# airball_sensor_board_v8_main.net
KiCad netlist of a schematic drawn in EAGLE
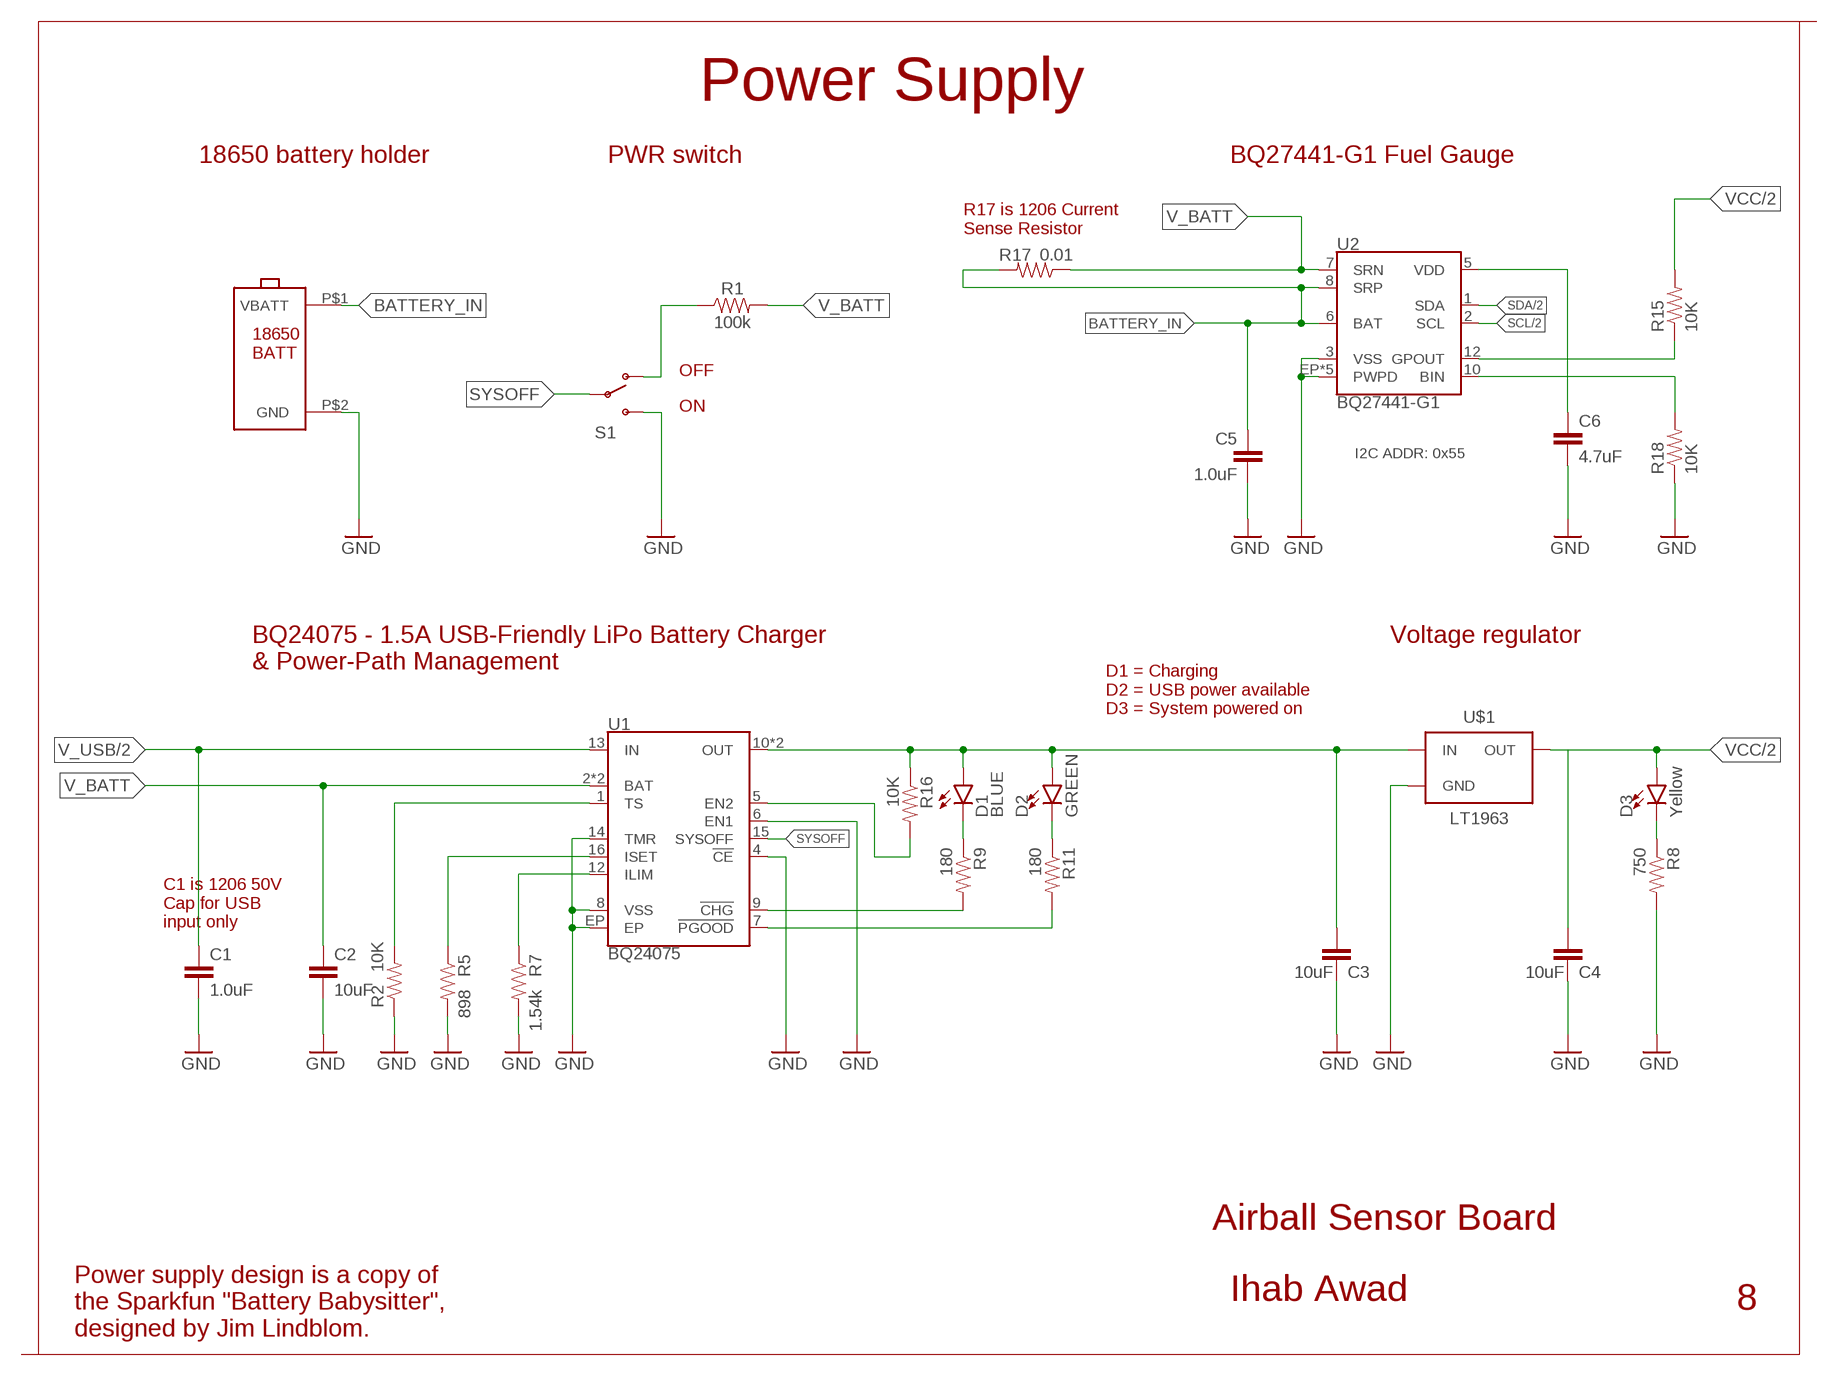
[diagram p0: schematic, sheet 1]
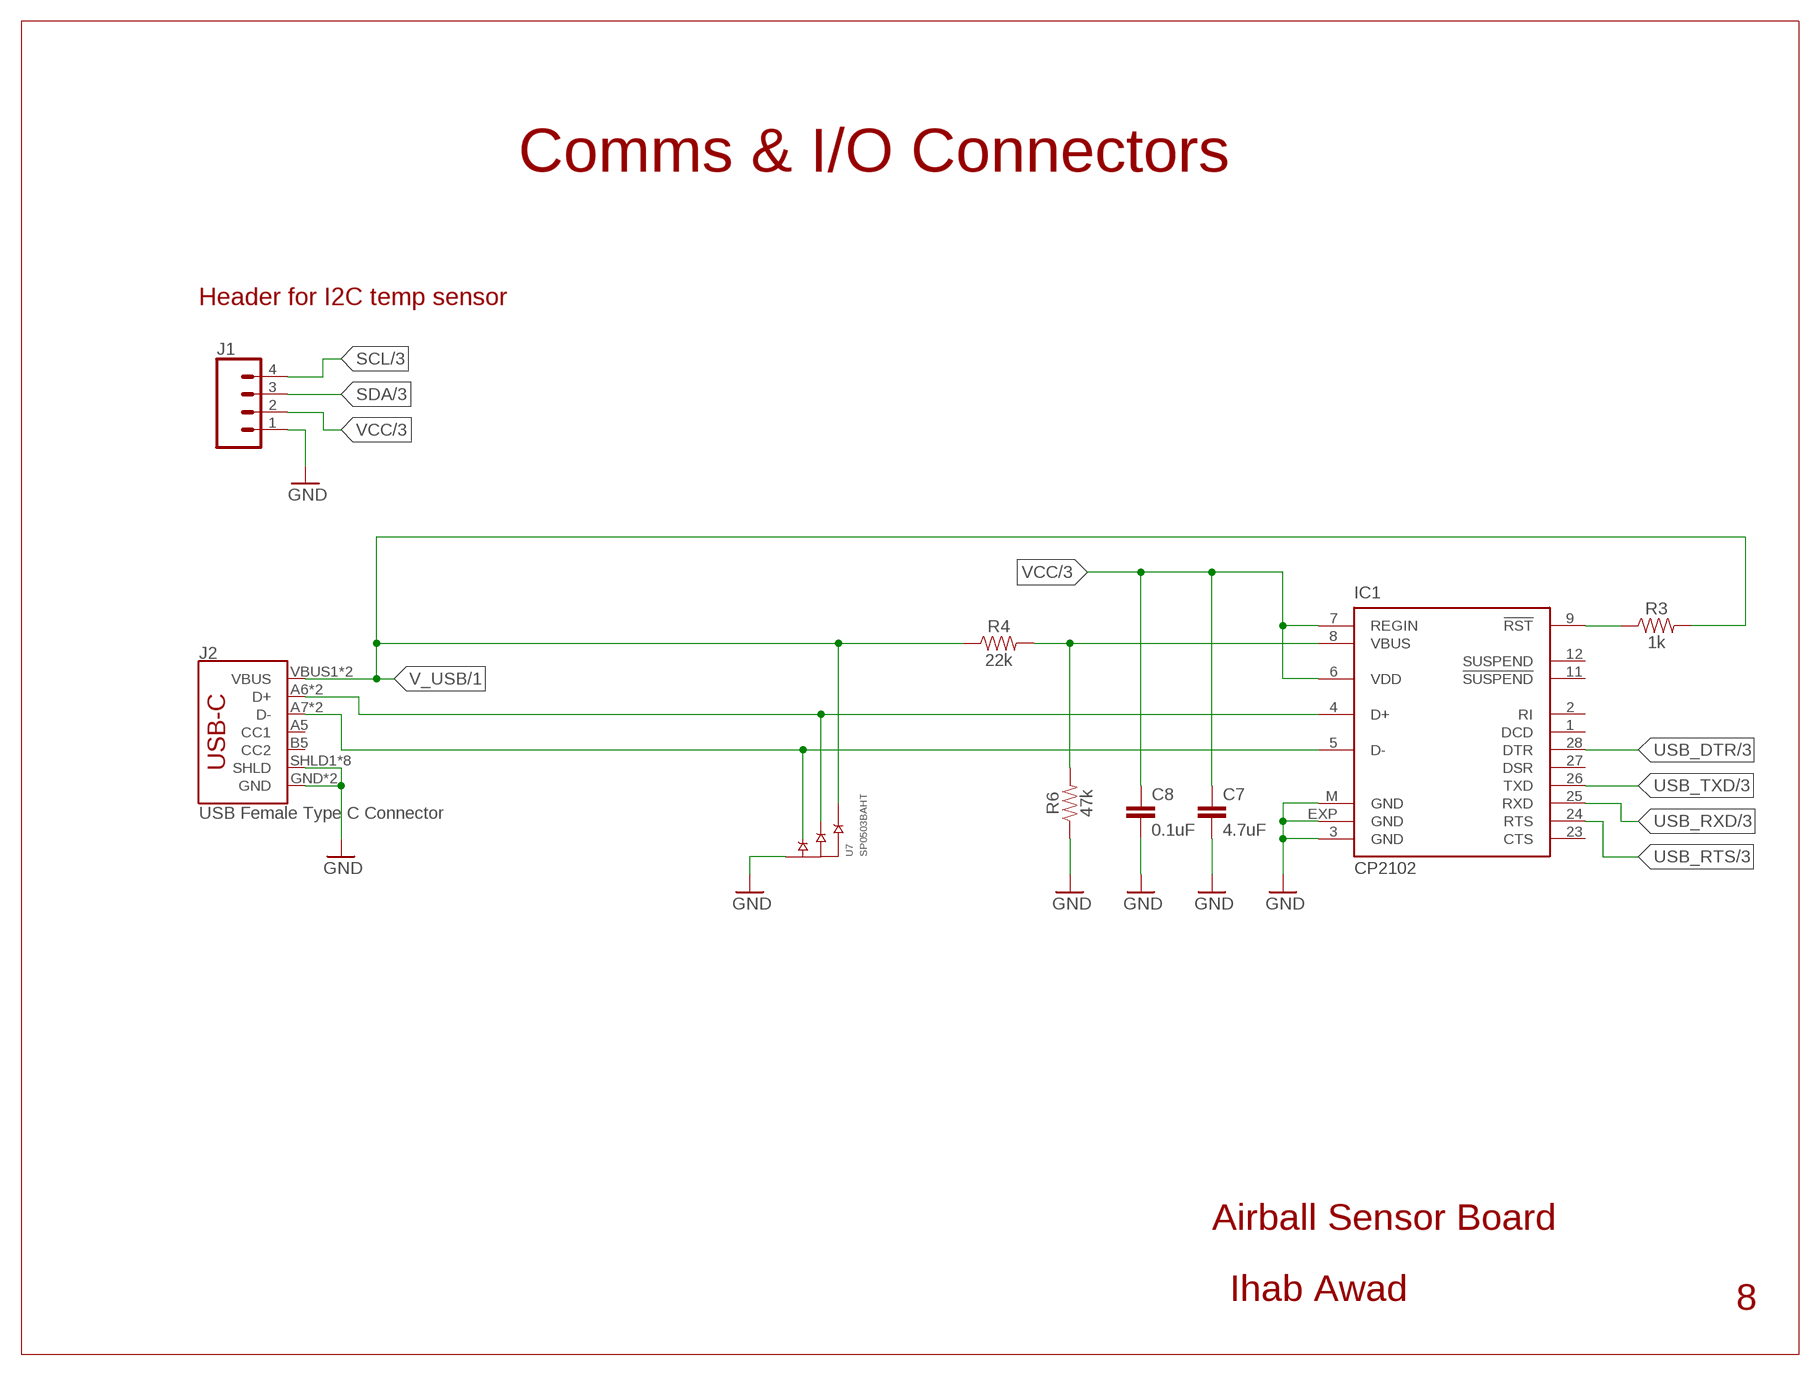
[diagram p1: schematic, sheet 2]
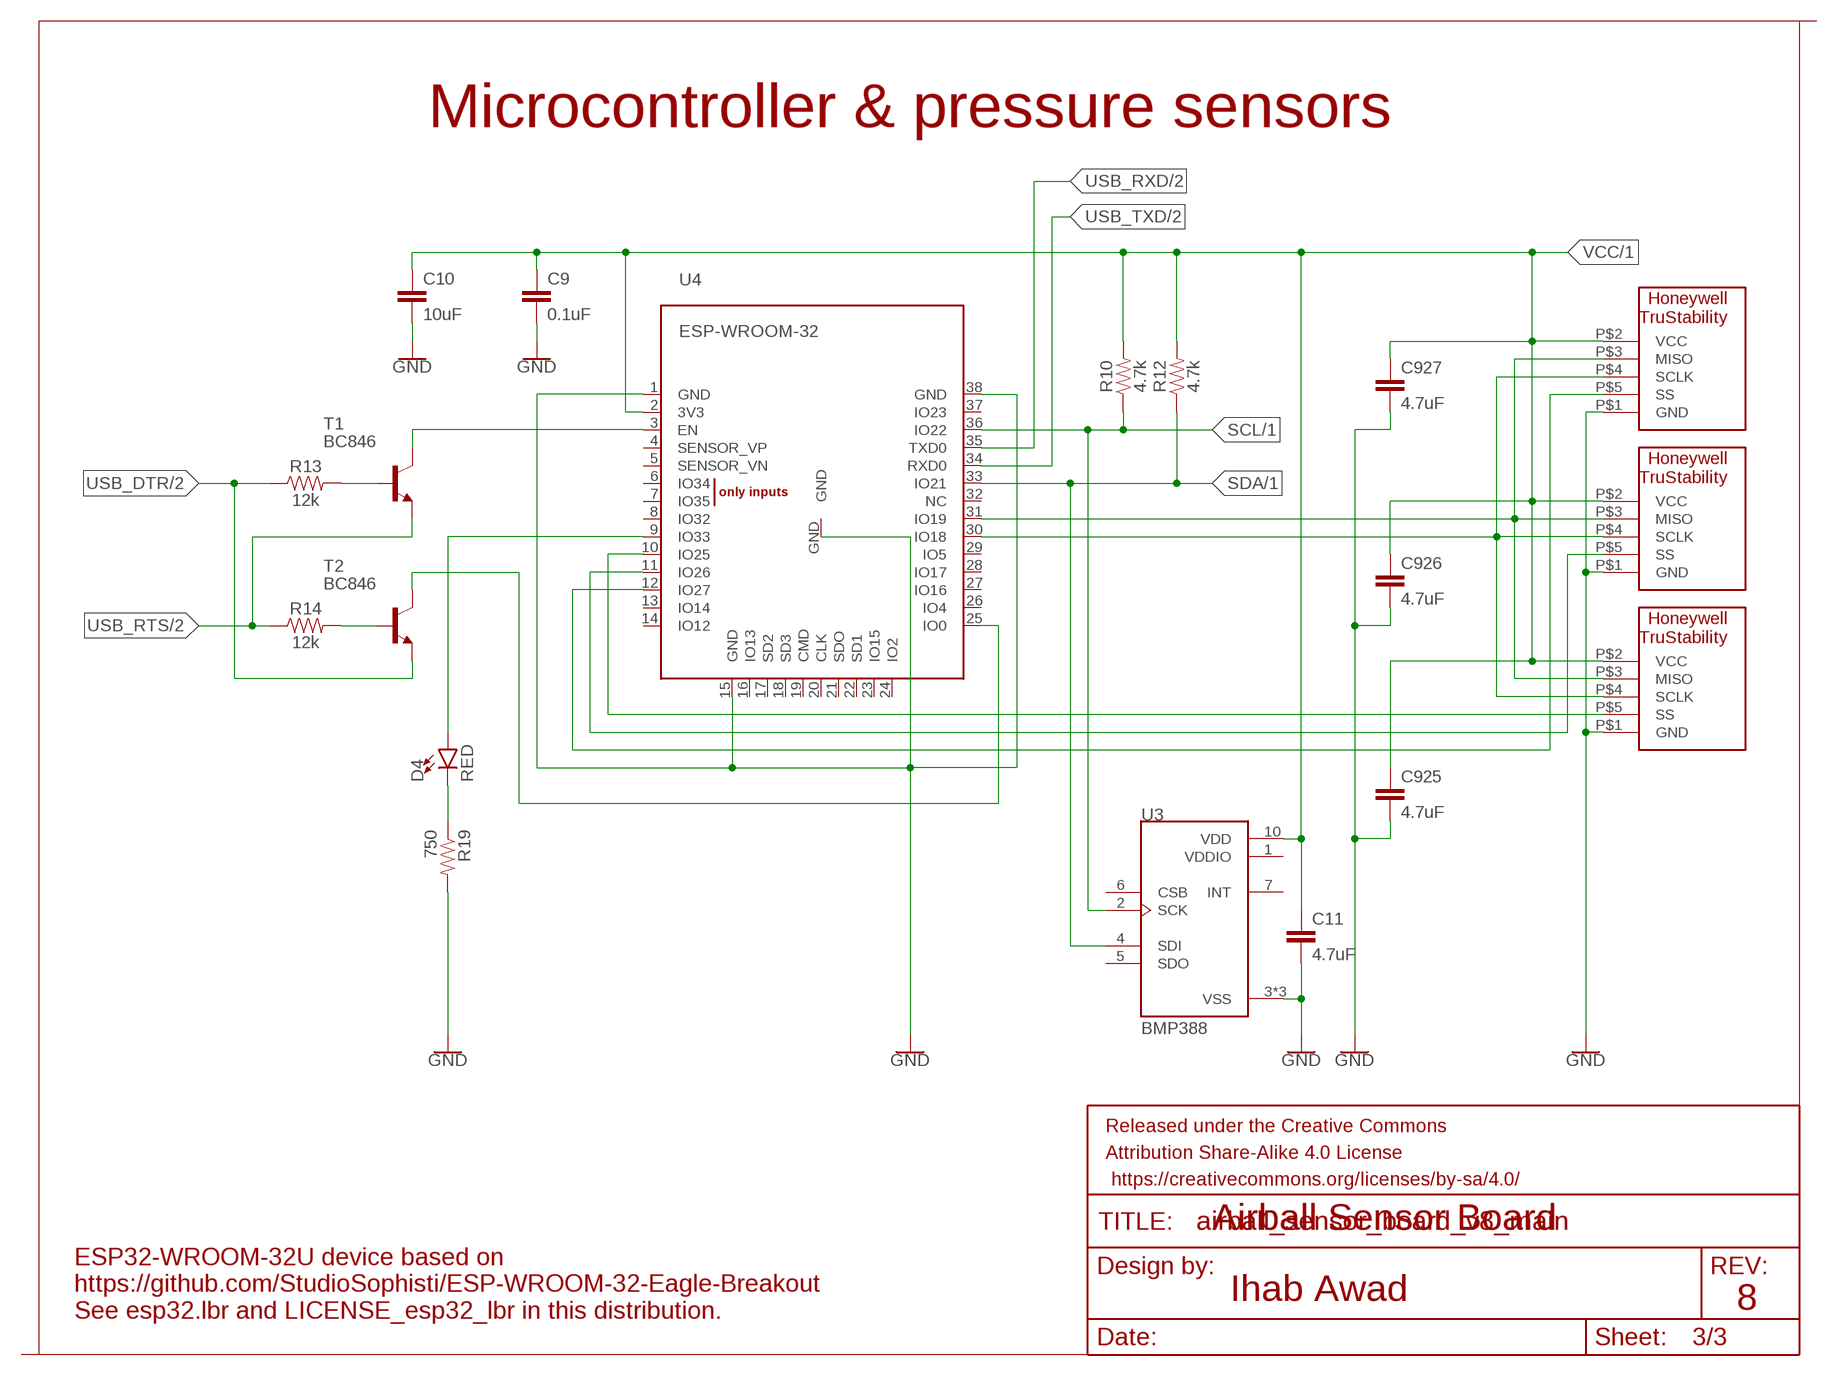
[diagram p2: schematic, sheet 3]

(export (version "E")
  (design (tool "Eeschema 10.0.6"))
  (components
    (comp (ref "C7")
      (value "4.7uF")
      (footprint "eagle-import:0603")
      (libsource (lib "eagle-import") (part "4.7UF-0603-35V-(20%)"))
    )
    (comp (ref "C8")
      (value "0.1uF")
      (footprint "eagle-import:0603")
      (libsource (lib "eagle-import") (part "0.1UF-0603-25V-(+80/-20%)"))
    )
    (comp (ref "IC1")
      (value "CP2102")
      (footprint "eagle-import:MLP28")
      (fields (field (name "MF") "FARNELL") (field (name "MPN") "CP2102-GM"))
      (libsource (lib "eagle-import") (part "CP2102"))
    )
    (comp (ref "J1")
      (value "CONN_04JST-PTH")
      (footprint "eagle-import:JST-4-PTH")
      (libsource (lib "eagle-import") (part "CONN_04JST-PTH"))
    )
    (comp (ref "J2")
      (value "USB Female Type C Connector")
      (footprint "eagle-import:USB-C-16P")
      (libsource (lib "eagle-import") (part "USB_C"))
    )
    (comp (ref "R3")
      (value "1k")
      (footprint "eagle-import:0603")
      (libsource (lib "eagle-import") (part "1KOHM-0603-1/10W-1%"))
    )
    (comp (ref "R4")
      (value "22k")
      (footprint "eagle-import:0603")
      (libsource (lib "eagle-import") (part "22KOHM-0603-1/10W-1%"))
    )
    (comp (ref "R6")
      (value "47k")
      (footprint "eagle-import:0603")
      (libsource (lib "eagle-import") (part "47KOHM-0603-1/10W-1%"))
    )
    (comp (ref "U7")
      (value "SP0503BAHT")
      (footprint "eagle-import:SOT143")
      (fields (field (name "DIGI-KEY_PART_NUMBER") "F2715TR-ND") (field (name "MF") "Littelfuse Inc."))
      (libsource (lib "eagle-import") (part "SP0503BAHT"))
    )
    (comp (ref "C9")
      (value "0.1uF")
      (footprint "eagle-import:0603")
      (libsource (lib "eagle-import") (part "0.1UF-0603-25V-(+80/-20%)"))
    )
    (comp (ref "C10")
      (value "10uF")
      (footprint "eagle-import:0603")
      (libsource (lib "eagle-import") (part "10UF-0603-6.3V-20%"))
    )
    (comp (ref "C11")
      (value "4.7uF")
      (footprint "eagle-import:0603")
      (libsource (lib "eagle-import") (part "4.7UF-0603-6.3V-(10%)"))
    )
    (comp (ref "C925")
      (value "4.7uF")
      (footprint "eagle-import:0603")
      (libsource (lib "eagle-import") (part "4.7UF-0603-6.3V-(10%)"))
    )
    (comp (ref "C926")
      (value "4.7uF")
      (footprint "eagle-import:0603")
      (libsource (lib "eagle-import") (part "4.7UF-0603-6.3V-(10%)"))
    )
    (comp (ref "C927")
      (value "4.7uF")
      (footprint "eagle-import:0603")
      (libsource (lib "eagle-import") (part "4.7UF-0603-6.3V-(10%)"))
    )
    (comp (ref "D4")
      (value "RED")
      (footprint "eagle-import:LED-0603")
      (libsource (lib "eagle-import") (part "LED-RED0603"))
    )
    (comp (ref "FRAME3")
      (value "FRAME-LETTER")
      (footprint "eagle-import:CREATIVE_COMMONS")
      (libsource (lib "eagle-import") (part "FRAME-LETTER"))
    )
    (comp (ref "R10")
      (value "4.7k")
      (footprint "eagle-import:0603")
      (libsource (lib "eagle-import") (part "4.7KOHM-0603-1/10W-1%"))
    )
    (comp (ref "R12")
      (value "4.7k")
      (footprint "eagle-import:0603")
      (libsource (lib "eagle-import") (part "4.7KOHM-0603-1/10W-1%"))
    )
    (comp (ref "R13")
      (value "12k")
      (footprint "eagle-import:0603")
      (libsource (lib "eagle-import") (part "12KOHM-0603-1/10W-1%"))
    )
    (comp (ref "R14")
      (value "12k")
      (footprint "eagle-import:0603")
      (libsource (lib "eagle-import") (part "12KOHM-0603-1/10W-1%"))
    )
    (comp (ref "R19")
      (value "750")
      (footprint "eagle-import:0603-RES")
      (libsource (lib "eagle-import") (part "10KOHM-1/10W-1%(0603)0603"))
    )
    (comp (ref "T1")
      (value "BC846")
      (footprint "eagle-import:SOT23")
      (libsource (lib "eagle-import") (part "BC846"))
    )
    (comp (ref "T2")
      (value "BC846")
      (footprint "eagle-import:SOT23")
      (libsource (lib "eagle-import") (part "BC846"))
    )
    (comp (ref "U$925")
      (value "HONEYWELL_HSC_SMT")
      (footprint "eagle-import:HONEYWELL_HSC_SMT")
      (libsource (lib "eagle-import") (part "HONEYWELL_HSC_SMT"))
    )
    (comp (ref "U$926")
      (value "HONEYWELL_HSC_SMT")
      (footprint "eagle-import:HONEYWELL_HSC_SMT")
      (libsource (lib "eagle-import") (part "HONEYWELL_HSC_SMT"))
    )
    (comp (ref "U$927")
      (value "HONEYWELL_HSC_SMT")
      (footprint "eagle-import:HONEYWELL_HSC_SMT")
      (libsource (lib "eagle-import") (part "HONEYWELL_HSC_SMT"))
    )
    (comp (ref "U3")
      (value "BMP388")
      (footprint "eagle-import:PQFN50P200X200X80-10N")
      (fields (field (name "MF") "Bosch Sensortec"))
      (libsource (lib "eagle-import") (part "BMP388"))
    )
    (comp (ref "U4")
      (value "ESP-WROOM-32")
      (footprint "eagle-import:ESP-WROOM-32")
      (libsource (lib "eagle-import") (part "ESP-WROOM-32"))
    )
    (comp (ref "C1")
      (value "1.0uF")
      (footprint "eagle-import:1206-CAP")
      (libsource (lib "eagle-import") (part "1.0UF50V10%(1206)"))
    )
    (comp (ref "C2")
      (value "10uF")
      (footprint "eagle-import:0805-CAP")
      (libsource (lib "eagle-import") (part "10UF10V10%(0805)"))
    )
    (comp (ref "C3")
      (value "10uF")
      (footprint "eagle-import:0805-CAP")
      (libsource (lib "eagle-import") (part "10UF10V10%(0805)"))
    )
    (comp (ref "C4")
      (value "10uF")
      (footprint "eagle-import:0805-CAP")
      (libsource (lib "eagle-import") (part "10UF10V10%(0805)"))
    )
    (comp (ref "C5")
      (value "1.0uF")
      (footprint "eagle-import:0603-CAP")
      (libsource (lib "eagle-import") (part "1.0UF-16V-10%(0603)"))
    )
    (comp (ref "C6")
      (value "4.7uF")
      (footprint "eagle-import:0603")
      (libsource (lib "eagle-import") (part "4.7UF-0603-35V-(20%)"))
    )
    (comp (ref "D1")
      (value "BLUE")
      (footprint "eagle-import:LED-0603")
      (libsource (lib "eagle-import") (part "LED-BLUE0603"))
    )
    (comp (ref "D2")
      (value "GREEN")
      (footprint "eagle-import:LED-0603")
      (libsource (lib "eagle-import") (part "LED-GREEN0603"))
    )
    (comp (ref "D3")
      (value "Yellow")
      (footprint "eagle-import:LED-0603")
      (libsource (lib "eagle-import") (part "LED-YELLOW0603"))
    )
    (comp (ref "R1")
      (value "100k")
      (footprint "eagle-import:0603")
      (libsource (lib "eagle-import") (part "100KOHM-0603-1/10W-1%"))
    )
    (comp (ref "R2")
      (value "10K")
      (footprint "eagle-import:0603-RES")
      (libsource (lib "eagle-import") (part "10KOHM-1/10W-1%(0603)0603"))
    )
    (comp (ref "R5")
      (value "898")
      (footprint "eagle-import:0603-RES")
      (libsource (lib "eagle-import") (part "RESISTOR0603-RES"))
    )
    (comp (ref "R7")
      (value "1.54k")
      (footprint "eagle-import:0603-RES")
      (libsource (lib "eagle-import") (part "RESISTOR0603-RES"))
    )
    (comp (ref "R8")
      (value "750")
      (footprint "eagle-import:0603-RES")
      (libsource (lib "eagle-import") (part "10KOHM-1/10W-1%(0603)0603"))
    )
    (comp (ref "R9")
      (value "180")
      (footprint "eagle-import:0603-RES")
      (libsource (lib "eagle-import") (part "180OHM1/10W1%(0603)"))
    )
    (comp (ref "R11")
      (value "180")
      (footprint "eagle-import:0603-RES")
      (libsource (lib "eagle-import") (part "180OHM1/10W1%(0603)"))
    )
    (comp (ref "R15")
      (value "10K")
      (footprint "eagle-import:0603-RES")
      (libsource (lib "eagle-import") (part "10KOHM-1/10W-1%(0603)0603"))
    )
    (comp (ref "R16")
      (value "10K")
      (footprint "eagle-import:0603-RES")
      (libsource (lib "eagle-import") (part "10KOHM-1/10W-1%(0603)0603"))
    )
    (comp (ref "R17")
      (value "0.01")
      (footprint "eagle-import:1206")
      (libsource (lib "eagle-import") (part "SparkFun-Resistors_RESISTOR1206"))
    )
    (comp (ref "R18")
      (value "10K")
      (footprint "eagle-import:0603-RES")
      (libsource (lib "eagle-import") (part "10KOHM-1/10W-1%(0603)0603"))
    )
    (comp (ref "S1")
      (value "SWITCH-SPDTSMD")
      (footprint "eagle-import:SWITCH_SPDT_SMD")
      (libsource (lib "eagle-import") (part "SWITCH-SPDTSMD"))
    )
    (comp (ref "U$1")
      (value "LT1963")
      (footprint "eagle-import:SOT223-3")
      (libsource (lib "eagle-import") (part "LT1963"))
    )
    (comp (ref "U$2")
      (value "KEYSTONE_1042P_18650_BATT_HOLDER")
      (footprint "eagle-import:KEYSTONE_1042P_18650_BATT_HOLDER")
      (libsource (lib "eagle-import") (part "KEYSTONE_1042P_18650_BATT_HOLDER"))
    )
    (comp (ref "U1")
      (value "BQ24075")
      (footprint "eagle-import:PVQFN-N16")
      (libsource (lib "eagle-import") (part "BQ24075"))
    )
    (comp (ref "U2")
      (value "BQ27441-G1")
      (footprint "eagle-import:PDSO-N12")
      (libsource (lib "eagle-import") (part "BQ27441-G1"))
    )
  )
  (nets
    (net (code "1") (name "BATTERY_IN") (class "Default")
      (node (ref "C5") (pin "1") (pinfunction "1_1") (pintype "passive"))
      (node (ref "R17") (pin "2") (pinfunction "2_2") (pintype "passive"))
      (node (ref "U$2") (pin "P$1") (pinfunction "VBATT_P$1") (pintype "bidirectional"))
      (node (ref "U2") (pin "6") (pinfunction "BAT_6") (pintype "bidirectional"))
      (node (ref "U2") (pin "8") (pinfunction "SRP_8") (pintype "bidirectional"))
    )
    (net (code "2") (name "GND") (class "Default")
      (node (ref "C1") (pin "2") (pinfunction "2_2") (pintype "passive"))
      (node (ref "C10") (pin "2") (pinfunction "2_2") (pintype "passive"))
      (node (ref "C11") (pin "2") (pinfunction "2_2") (pintype "passive"))
      (node (ref "C2") (pin "2") (pinfunction "2_2") (pintype "passive"))
      (node (ref "C3") (pin "2") (pinfunction "2_2") (pintype "passive"))
      (node (ref "C4") (pin "2") (pinfunction "2_2") (pintype "passive"))
      (node (ref "C5") (pin "2") (pinfunction "2_2") (pintype "passive"))
      (node (ref "C6") (pin "2") (pinfunction "2_2") (pintype "passive"))
      (node (ref "C7") (pin "2") (pinfunction "2_2") (pintype "passive"))
      (node (ref "C8") (pin "2") (pinfunction "2_2") (pintype "passive"))
      (node (ref "C9") (pin "2") (pinfunction "2_2") (pintype "passive"))
      (node (ref "C925") (pin "2") (pinfunction "2_2") (pintype "passive"))
      (node (ref "C926") (pin "2") (pinfunction "2_2") (pintype "passive"))
      (node (ref "C927") (pin "2") (pinfunction "2_2") (pintype "passive"))
      (node (ref "IC1") (pin "3") (pinfunction "GND_3") (pintype "power_in"))
      (node (ref "IC1") (pin "EXP") (pinfunction "GND_EXP") (pintype "power_in"))
      (node (ref "IC1") (pin "M") (pinfunction "GND_M") (pintype "power_in"))
      (node (ref "J1") (pin "1") (pinfunction "1_1") (pintype "passive"))
      (node (ref "J2") (pin "GND") (pinfunction "GND_GND") (pintype "bidirectional"))
      (node (ref "J2") (pin "GND2") (pinfunction "GND_GND2") (pintype "bidirectional"))
      (node (ref "J2") (pin "SHLD1") (pinfunction "SHLD_SHLD1") (pintype "bidirectional"))
      (node (ref "J2") (pin "SHLD2") (pinfunction "SHLD_SHLD2") (pintype "bidirectional"))
      (node (ref "J2") (pin "SHLD3") (pinfunction "SHLD_SHLD3") (pintype "bidirectional"))
      (node (ref "J2") (pin "SHLD4") (pinfunction "SHLD_SHLD4") (pintype "bidirectional"))
      (node (ref "J2") (pin "SHLD5") (pinfunction "SHLD_SHLD5") (pintype "bidirectional"))
      (node (ref "J2") (pin "SHLD6") (pinfunction "SHLD_SHLD6") (pintype "bidirectional"))
      (node (ref "J2") (pin "SHLD7") (pinfunction "SHLD_SHLD7") (pintype "bidirectional"))
      (node (ref "J2") (pin "SHLD8") (pinfunction "SHLD_SHLD8") (pintype "bidirectional"))
      (node (ref "R18") (pin "1") (pinfunction "1_1") (pintype "passive"))
      (node (ref "R19") (pin "2") (pinfunction "2_2") (pintype "passive"))
      (node (ref "R2") (pin "1") (pinfunction "1_1") (pintype "passive"))
      (node (ref "R5") (pin "2") (pinfunction "2_2") (pintype "passive"))
      (node (ref "R6") (pin "1") (pinfunction "1_1") (pintype "passive"))
      (node (ref "R7") (pin "2") (pinfunction "2_2") (pintype "passive"))
      (node (ref "R8") (pin "2") (pinfunction "2_2") (pintype "passive"))
      (node (ref "S1") (pin "3") (pinfunction "S_3") (pintype "passive"))
      (node (ref "U$1") (pin "2") (pinfunction "GND_2") (pintype "power_in"))
      (node (ref "U$1") (pin "TAB") (pinfunction "GND_TAB") (pintype "power_in"))
      (node (ref "U$2") (pin "P$2") (pinfunction "GND_P$2") (pintype "bidirectional"))
      (node (ref "U$925") (pin "P$1") (pinfunction "GND_P$1") (pintype "bidirectional"))
      (node (ref "U$926") (pin "P$1") (pinfunction "GND_P$1") (pintype "bidirectional"))
      (node (ref "U$927") (pin "P$1") (pinfunction "GND_P$1") (pintype "bidirectional"))
      (node (ref "U1") (pin "14") (pinfunction "TMR_14") (pintype "bidirectional"))
      (node (ref "U1") (pin "4") (pinfunction "~{CE}_4") (pintype "bidirectional"))
      (node (ref "U1") (pin "6") (pinfunction "EN1_6") (pintype "bidirectional"))
      (node (ref "U1") (pin "8") (pinfunction "VSS_8") (pintype "bidirectional"))
      (node (ref "U1") (pin "EP") (pinfunction "EP_EP") (pintype "bidirectional"))
      (node (ref "U2") (pin "3") (pinfunction "VSS_3") (pintype "bidirectional"))
      (node (ref "U2") (pin "EP") (pinfunction "PWPD_EP") (pintype "bidirectional"))
      (node (ref "U2") (pin "EP1") (pinfunction "PWPD_EP1") (pintype "bidirectional"))
      (node (ref "U2") (pin "EP2") (pinfunction "PWPD_EP2") (pintype "bidirectional"))
      (node (ref "U2") (pin "EP3") (pinfunction "PWPD_EP3") (pintype "bidirectional"))
      (node (ref "U2") (pin "EP4") (pinfunction "PWPD_EP4") (pintype "bidirectional"))
      (node (ref "U3") (pin "3") (pinfunction "VSS_3") (pintype "power_in"))
      (node (ref "U3") (pin "8") (pinfunction "VSS_8") (pintype "power_in"))
      (node (ref "U3") (pin "9") (pinfunction "VSS_9") (pintype "power_in"))
      (node (ref "U4") (pin "1") (pinfunction "GND_1") (pintype "bidirectional"))
      (node (ref "U4") (pin "15") (pinfunction "GND_15") (pintype "bidirectional"))
      (node (ref "U4") (pin "38") (pinfunction "GND_38") (pintype "bidirectional"))
      (node (ref "U4") (pin "GND") (pinfunction "GND_GND") (pintype "bidirectional"))
      (node (ref "U7") (pin "1") (pinfunction "GND_1") (pintype "bidirectional"))
    )
    (net (code "3") (name "Net-(D1-PadC)") (class "Default")
      (node (ref "D1") (pin "C") (pinfunction "C_C") (pintype "passive"))
      (node (ref "R9") (pin "1") (pinfunction "1_1") (pintype "passive"))
    )
    (net (code "4") (name "Net-(D2-PadC)") (class "Default")
      (node (ref "D2") (pin "C") (pinfunction "C_C") (pintype "passive"))
      (node (ref "R11") (pin "1") (pinfunction "1_1") (pintype "passive"))
    )
    (net (code "5") (name "Net-(D3-PadC)") (class "Default")
      (node (ref "D3") (pin "C") (pinfunction "C_C") (pintype "passive"))
      (node (ref "R8") (pin "1") (pinfunction "1_1") (pintype "passive"))
    )
    (net (code "6") (name "Net-(D4-PadC)") (class "Default")
      (node (ref "D4") (pin "C") (pinfunction "C_C") (pintype "passive"))
      (node (ref "R19") (pin "1") (pinfunction "1_1") (pintype "passive"))
    )
    (net (code "7") (name "Net-(IC1-D+)") (class "Default")
      (node (ref "IC1") (pin "4") (pinfunction "D+_4") (pintype "bidirectional"))
      (node (ref "J2") (pin "A6") (pinfunction "D+_A6") (pintype "bidirectional"))
      (node (ref "J2") (pin "B6") (pinfunction "D+_B6") (pintype "bidirectional"))
      (node (ref "U7") (pin "3") (pinfunction "B_3") (pintype "bidirectional"))
    )
    (net (code "8") (name "Net-(IC1-D-)") (class "Default")
      (node (ref "IC1") (pin "5") (pinfunction "D-_5") (pintype "bidirectional"))
      (node (ref "J2") (pin "A7") (pinfunction "D-_A7") (pintype "bidirectional"))
      (node (ref "J2") (pin "B7") (pinfunction "D-_B7") (pintype "bidirectional"))
      (node (ref "U7") (pin "2") (pinfunction "A_2") (pintype "bidirectional"))
    )
    (net (code "9") (name "Net-(IC1-VBUS)") (class "Default")
      (node (ref "IC1") (pin "8") (pinfunction "VBUS_8") (pintype "input"))
      (node (ref "R4") (pin "2") (pinfunction "2_2") (pintype "passive"))
      (node (ref "R6") (pin "2") (pinfunction "2_2") (pintype "passive"))
    )
    (net (code "10") (name "Net-(IC1-~{RST})") (class "Default")
      (node (ref "IC1") (pin "9") (pinfunction "~{RST}_9") (pintype "bidirectional"))
      (node (ref "R3") (pin "1") (pinfunction "1_1") (pintype "passive"))
    )
    (net (code "11") (name "Net-(S1-O)") (class "Default")
      (node (ref "R1") (pin "1") (pinfunction "1_1") (pintype "passive"))
      (node (ref "S1") (pin "1") (pinfunction "O_1") (pintype "passive"))
    )
    (net (code "12") (name "Net-(T1-B)") (class "Default")
      (node (ref "R13") (pin "2") (pinfunction "2_2") (pintype "passive"))
      (node (ref "T1") (pin "1") (pinfunction "B_1") (pintype "passive"))
    )
    (net (code "13") (name "Net-(T1-C)") (class "Default")
      (node (ref "T1") (pin "3") (pinfunction "C_3") (pintype "passive"))
      (node (ref "U4") (pin "3") (pinfunction "EN_3") (pintype "bidirectional"))
    )
    (net (code "14") (name "Net-(T2-B)") (class "Default")
      (node (ref "R14") (pin "2") (pinfunction "2_2") (pintype "passive"))
      (node (ref "T2") (pin "1") (pinfunction "B_1") (pintype "passive"))
    )
    (net (code "15") (name "Net-(T2-C)") (class "Default")
      (node (ref "T2") (pin "3") (pinfunction "C_3") (pintype "passive"))
      (node (ref "U4") (pin "25") (pinfunction "IO0_25") (pintype "bidirectional"))
    )
    (net (code "16") (name "Net-(U$1-IN)") (class "Default")
      (node (ref "C3") (pin "1") (pinfunction "1_1") (pintype "passive"))
      (node (ref "D1") (pin "A") (pinfunction "A_A") (pintype "passive"))
      (node (ref "D2") (pin "A") (pinfunction "A_A") (pintype "passive"))
      (node (ref "R16") (pin "1") (pinfunction "1_1") (pintype "passive"))
      (node (ref "U$1") (pin "1") (pinfunction "IN_1") (pintype "power_in"))
      (node (ref "U1") (pin "10") (pinfunction "OUT_10") (pintype "bidirectional"))
      (node (ref "U1") (pin "11") (pinfunction "OUT_11") (pintype "bidirectional"))
    )
    (net (code "17") (name "Net-(U$925-MISO)") (class "Default")
      (node (ref "U$925") (pin "P$3") (pinfunction "MISO_P$3") (pintype "bidirectional"))
      (node (ref "U$926") (pin "P$3") (pinfunction "MISO_P$3") (pintype "bidirectional"))
      (node (ref "U$927") (pin "P$3") (pinfunction "MISO_P$3") (pintype "bidirectional"))
      (node (ref "U4") (pin "31") (pinfunction "IO19_31") (pintype "bidirectional"))
    )
    (net (code "18") (name "Net-(U$925-SCLK)") (class "Default")
      (node (ref "U$925") (pin "P$4") (pinfunction "SCLK_P$4") (pintype "bidirectional"))
      (node (ref "U$926") (pin "P$4") (pinfunction "SCLK_P$4") (pintype "bidirectional"))
      (node (ref "U$927") (pin "P$4") (pinfunction "SCLK_P$4") (pintype "bidirectional"))
      (node (ref "U4") (pin "30") (pinfunction "IO18_30") (pintype "bidirectional"))
    )
    (net (code "19") (name "Net-(U$925-SS)") (class "Default")
      (node (ref "U$925") (pin "P$5") (pinfunction "SS_P$5") (pintype "bidirectional"))
      (node (ref "U4") (pin "10") (pinfunction "IO25_10") (pintype "bidirectional"))
    )
    (net (code "20") (name "Net-(U$926-SS)") (class "Default")
      (node (ref "U$926") (pin "P$5") (pinfunction "SS_P$5") (pintype "bidirectional"))
      (node (ref "U4") (pin "11") (pinfunction "IO26_11") (pintype "bidirectional"))
    )
    (net (code "21") (name "Net-(U$927-SS)") (class "Default")
      (node (ref "U$927") (pin "P$5") (pinfunction "SS_P$5") (pintype "bidirectional"))
      (node (ref "U4") (pin "12") (pinfunction "IO27_12") (pintype "bidirectional"))
    )
    (net (code "22") (name "Net-(U1-EN2)") (class "Default")
      (node (ref "R16") (pin "2") (pinfunction "2_2") (pintype "passive"))
      (node (ref "U1") (pin "5") (pinfunction "EN2_5") (pintype "bidirectional"))
    )
    (net (code "23") (name "Net-(U1-ILIM)") (class "Default")
      (node (ref "R7") (pin "1") (pinfunction "1_1") (pintype "passive"))
      (node (ref "U1") (pin "12") (pinfunction "ILIM_12") (pintype "bidirectional"))
    )
    (net (code "24") (name "Net-(U1-ISET)") (class "Default")
      (node (ref "R5") (pin "1") (pinfunction "1_1") (pintype "passive"))
      (node (ref "U1") (pin "16") (pinfunction "ISET_16") (pintype "bidirectional"))
    )
    (net (code "25") (name "Net-(U1-TS)") (class "Default")
      (node (ref "R2") (pin "2") (pinfunction "2_2") (pintype "passive"))
      (node (ref "U1") (pin "1") (pinfunction "TS_1") (pintype "bidirectional"))
    )
    (net (code "26") (name "Net-(U1-~{CHG})") (class "Default")
      (node (ref "R9") (pin "2") (pinfunction "2_2") (pintype "passive"))
      (node (ref "U1") (pin "9") (pinfunction "~{CHG}_9") (pintype "bidirectional"))
    )
    (net (code "27") (name "Net-(U1-~{PGOOD})") (class "Default")
      (node (ref "R11") (pin "2") (pinfunction "2_2") (pintype "passive"))
      (node (ref "U1") (pin "7") (pinfunction "~{PGOOD}_7") (pintype "bidirectional"))
    )
    (net (code "28") (name "Net-(U2-BIN)") (class "Default")
      (node (ref "R18") (pin "2") (pinfunction "2_2") (pintype "passive"))
      (node (ref "U2") (pin "10") (pinfunction "BIN_10") (pintype "bidirectional"))
    )
    (net (code "29") (name "Net-(U2-GPOUT)") (class "Default")
      (node (ref "R15") (pin "1") (pinfunction "1_1") (pintype "passive"))
      (node (ref "U2") (pin "12") (pinfunction "GPOUT_12") (pintype "bidirectional"))
    )
    (net (code "30") (name "Net-(U2-VDD)") (class "Default")
      (node (ref "C6") (pin "1") (pinfunction "1_1") (pintype "passive"))
      (node (ref "U2") (pin "5") (pinfunction "VDD_5") (pintype "bidirectional"))
    )
    (net (code "31") (name "Net-(U4-IO33)") (class "Default")
      (node (ref "D4") (pin "A") (pinfunction "A_A") (pintype "passive"))
      (node (ref "U4") (pin "9") (pinfunction "IO33_9") (pintype "bidirectional"))
    )
    (net (code "32") (name "SCL") (class "Default")
      (node (ref "J1") (pin "4") (pinfunction "4_4") (pintype "passive"))
      (node (ref "R10") (pin "1") (pinfunction "1_1") (pintype "passive"))
      (node (ref "U2") (pin "2") (pinfunction "SCL_2") (pintype "bidirectional"))
      (node (ref "U3") (pin "2") (pinfunction "SCK_2") (pintype "input"))
      (node (ref "U4") (pin "36") (pinfunction "IO22_36") (pintype "bidirectional"))
    )
    (net (code "33") (name "SDA") (class "Default")
      (node (ref "J1") (pin "3") (pinfunction "3_3") (pintype "passive"))
      (node (ref "R12") (pin "1") (pinfunction "1_1") (pintype "passive"))
      (node (ref "U2") (pin "1") (pinfunction "SDA_1") (pintype "bidirectional"))
      (node (ref "U3") (pin "4") (pinfunction "SDI_4") (pintype "bidirectional"))
      (node (ref "U4") (pin "33") (pinfunction "IO21_33") (pintype "bidirectional"))
    )
    (net (code "34") (name "SYSOFF") (class "Default")
      (node (ref "S1") (pin "2") (pinfunction "P_2") (pintype "passive"))
      (node (ref "U1") (pin "15") (pinfunction "SYSOFF_15") (pintype "bidirectional"))
    )
    (net (code "35") (name "USB_DTR") (class "Default")
      (node (ref "IC1") (pin "28") (pinfunction "DTR_28") (pintype "output"))
      (node (ref "R13") (pin "1") (pinfunction "1_1") (pintype "passive"))
      (node (ref "T2") (pin "2") (pinfunction "E_2") (pintype "passive"))
    )
    (net (code "36") (name "USB_RTS") (class "Default")
      (node (ref "IC1") (pin "24") (pinfunction "RTS_24") (pintype "output"))
      (node (ref "R14") (pin "1") (pinfunction "1_1") (pintype "passive"))
      (node (ref "T1") (pin "2") (pinfunction "E_2") (pintype "passive"))
    )
    (net (code "37") (name "USB_RXD") (class "Default")
      (node (ref "IC1") (pin "25") (pinfunction "RXD_25") (pintype "input"))
      (node (ref "U4") (pin "35") (pinfunction "TXD0_35") (pintype "bidirectional"))
    )
    (net (code "38") (name "USB_TXD") (class "Default")
      (node (ref "IC1") (pin "26") (pinfunction "TXD_26") (pintype "output"))
      (node (ref "U4") (pin "34") (pinfunction "RXD0_34") (pintype "bidirectional"))
    )
    (net (code "39") (name "VCC") (class "Default")
      (node (ref "C10") (pin "1") (pinfunction "1_1") (pintype "passive"))
      (node (ref "C11") (pin "1") (pinfunction "1_1") (pintype "passive"))
      (node (ref "C4") (pin "1") (pinfunction "1_1") (pintype "passive"))
      (node (ref "C7") (pin "1") (pinfunction "1_1") (pintype "passive"))
      (node (ref "C8") (pin "1") (pinfunction "1_1") (pintype "passive"))
      (node (ref "C9") (pin "1") (pinfunction "1_1") (pintype "passive"))
      (node (ref "C925") (pin "1") (pinfunction "1_1") (pintype "passive"))
      (node (ref "C926") (pin "1") (pinfunction "1_1") (pintype "passive"))
      (node (ref "C927") (pin "1") (pinfunction "1_1") (pintype "passive"))
      (node (ref "D3") (pin "A") (pinfunction "A_A") (pintype "passive"))
      (node (ref "IC1") (pin "6") (pinfunction "VDD_6") (pintype "power_in"))
      (node (ref "IC1") (pin "7") (pinfunction "REGIN_7") (pintype "passive"))
      (node (ref "J1") (pin "2") (pinfunction "2_2") (pintype "passive"))
      (node (ref "R10") (pin "2") (pinfunction "2_2") (pintype "passive"))
      (node (ref "R12") (pin "2") (pinfunction "2_2") (pintype "passive"))
      (node (ref "R15") (pin "2") (pinfunction "2_2") (pintype "passive"))
      (node (ref "U$1") (pin "3") (pinfunction "OUT_3") (pintype "power_in"))
      (node (ref "U$925") (pin "P$2") (pinfunction "VCC_P$2") (pintype "bidirectional"))
      (node (ref "U$926") (pin "P$2") (pinfunction "VCC_P$2") (pintype "bidirectional"))
      (node (ref "U$927") (pin "P$2") (pinfunction "VCC_P$2") (pintype "bidirectional"))
      (node (ref "U3") (pin "10") (pinfunction "VDD_10") (pintype "power_in"))
      (node (ref "U4") (pin "2") (pinfunction "3V3_2") (pintype "bidirectional"))
    )
    (net (code "40") (name "VDDIO") (class "Default")
      (node (ref "U3") (pin "1") (pinfunction "VDDIO_1") (pintype "power_in"))
    )
    (net (code "41") (name "V_BATT") (class "Default")
      (node (ref "C2") (pin "1") (pinfunction "1_1") (pintype "passive"))
      (node (ref "R1") (pin "2") (pinfunction "2_2") (pintype "passive"))
      (node (ref "R17") (pin "1") (pinfunction "1_1") (pintype "passive"))
      (node (ref "U1") (pin "2") (pinfunction "BAT_2") (pintype "bidirectional"))
      (node (ref "U1") (pin "3") (pinfunction "BAT_3") (pintype "bidirectional"))
      (node (ref "U2") (pin "7") (pinfunction "SRN_7") (pintype "bidirectional"))
    )
    (net (code "42") (name "V_USB") (class "Default")
      (node (ref "C1") (pin "1") (pinfunction "1_1") (pintype "passive"))
      (node (ref "J2") (pin "VBUS1") (pinfunction "VBUS_VBUS1") (pintype "bidirectional"))
      (node (ref "J2") (pin "VBUS2") (pinfunction "VBUS_VBUS2") (pintype "bidirectional"))
      (node (ref "R3") (pin "2") (pinfunction "2_2") (pintype "passive"))
      (node (ref "R4") (pin "1") (pinfunction "1_1") (pintype "passive"))
      (node (ref "U1") (pin "13") (pinfunction "IN_13") (pintype "bidirectional"))
      (node (ref "U7") (pin "4") (pinfunction "C_4") (pintype "bidirectional"))
    )
    (net (code "43") (name "unconnected-(IC1-CTS-Pad23)") (class "Default")
      (node (ref "IC1") (pin "23") (pinfunction "CTS_23") (pintype "input"))
    )
    (net (code "44") (name "unconnected-(IC1-DCD-Pad1)") (class "Default")
      (node (ref "IC1") (pin "1") (pinfunction "DCD_1") (pintype "input"))
    )
    (net (code "45") (name "unconnected-(IC1-DSR-Pad27)") (class "Default")
      (node (ref "IC1") (pin "27") (pinfunction "DSR_27") (pintype "input"))
    )
    (net (code "46") (name "unconnected-(IC1-RI-Pad2)") (class "Default")
      (node (ref "IC1") (pin "2") (pinfunction "RI_2") (pintype "input"))
    )
    (net (code "47") (name "unconnected-(IC1-SUSPEND-Pad12)") (class "Default")
      (node (ref "IC1") (pin "12") (pinfunction "SUSPEND_12") (pintype "output"))
    )
    (net (code "48") (name "unconnected-(IC1-~{SUSPEND}-Pad11)") (class "Default")
      (node (ref "IC1") (pin "11") (pinfunction "~{SUSPEND}_11") (pintype "output"))
    )
    (net (code "49") (name "unconnected-(J2-CC1-PadA5)") (class "Default")
      (node (ref "J2") (pin "A5") (pinfunction "CC1_A5") (pintype "bidirectional"))
    )
    (net (code "50") (name "unconnected-(J2-CC2-PadB5)") (class "Default")
      (node (ref "J2") (pin "B5") (pinfunction "CC2_B5") (pintype "bidirectional"))
    )
    (net (code "51") (name "unconnected-(U3-CSB-Pad6)") (class "Default")
      (node (ref "U3") (pin "6") (pinfunction "CSB_6") (pintype "input"))
    )
    (net (code "52") (name "unconnected-(U3-INT-Pad7)") (class "Default")
      (node (ref "U3") (pin "7") (pinfunction "INT_7") (pintype "output"))
    )
    (net (code "53") (name "unconnected-(U3-SDO-Pad5)") (class "Default")
      (node (ref "U3") (pin "5") (pinfunction "SDO_5") (pintype "bidirectional"))
    )
    (net (code "54") (name "unconnected-(U4-CLK-Pad20)") (class "Default")
      (node (ref "U4") (pin "20") (pinfunction "CLK_20") (pintype "bidirectional"))
    )
    (net (code "55") (name "unconnected-(U4-CMD-Pad19)") (class "Default")
      (node (ref "U4") (pin "19") (pinfunction "CMD_19") (pintype "bidirectional"))
    )
    (net (code "56") (name "unconnected-(U4-IO2-Pad24)") (class "Default")
      (node (ref "U4") (pin "24") (pinfunction "IO2_24") (pintype "bidirectional"))
    )
    (net (code "57") (name "unconnected-(U4-IO4-Pad26)") (class "Default")
      (node (ref "U4") (pin "26") (pinfunction "IO4_26") (pintype "bidirectional"))
    )
    (net (code "58") (name "unconnected-(U4-IO5-Pad29)") (class "Default")
      (node (ref "U4") (pin "29") (pinfunction "IO5_29") (pintype "bidirectional"))
    )
    (net (code "59") (name "unconnected-(U4-IO12-Pad14)") (class "Default")
      (node (ref "U4") (pin "14") (pinfunction "IO12_14") (pintype "bidirectional"))
    )
    (net (code "60") (name "unconnected-(U4-IO13-Pad16)") (class "Default")
      (node (ref "U4") (pin "16") (pinfunction "IO13_16") (pintype "bidirectional"))
    )
    (net (code "61") (name "unconnected-(U4-IO14-Pad13)") (class "Default")
      (node (ref "U4") (pin "13") (pinfunction "IO14_13") (pintype "bidirectional"))
    )
    (net (code "62") (name "unconnected-(U4-IO15-Pad23)") (class "Default")
      (node (ref "U4") (pin "23") (pinfunction "IO15_23") (pintype "bidirectional"))
    )
    (net (code "63") (name "unconnected-(U4-IO16-Pad27)") (class "Default")
      (node (ref "U4") (pin "27") (pinfunction "IO16_27") (pintype "bidirectional"))
    )
    (net (code "64") (name "unconnected-(U4-IO17-Pad28)") (class "Default")
      (node (ref "U4") (pin "28") (pinfunction "IO17_28") (pintype "bidirectional"))
    )
    (net (code "65") (name "unconnected-(U4-IO23-Pad37)") (class "Default")
      (node (ref "U4") (pin "37") (pinfunction "IO23_37") (pintype "bidirectional"))
    )
    (net (code "66") (name "unconnected-(U4-IO32-Pad8)") (class "Default")
      (node (ref "U4") (pin "8") (pinfunction "IO32_8") (pintype "bidirectional"))
    )
    (net (code "67") (name "unconnected-(U4-IO34-Pad6)") (class "Default")
      (node (ref "U4") (pin "6") (pinfunction "IO34_6") (pintype "input"))
    )
    (net (code "68") (name "unconnected-(U4-IO35-Pad7)") (class "Default")
      (node (ref "U4") (pin "7") (pinfunction "IO35_7") (pintype "input"))
    )
    (net (code "69") (name "unconnected-(U4-NC-Pad32)") (class "Default")
      (node (ref "U4") (pin "32") (pinfunction "NC_32") (pintype "bidirectional"))
    )
    (net (code "70") (name "unconnected-(U4-SD1-Pad22)") (class "Default")
      (node (ref "U4") (pin "22") (pinfunction "SD1_22") (pintype "bidirectional"))
    )
    (net (code "71") (name "unconnected-(U4-SD2-Pad17)") (class "Default")
      (node (ref "U4") (pin "17") (pinfunction "SD2_17") (pintype "bidirectional"))
    )
    (net (code "72") (name "unconnected-(U4-SD3-Pad18)") (class "Default")
      (node (ref "U4") (pin "18") (pinfunction "SD3_18") (pintype "bidirectional"))
    )
    (net (code "73") (name "unconnected-(U4-SDO-Pad21)") (class "Default")
      (node (ref "U4") (pin "21") (pinfunction "SDO_21") (pintype "bidirectional"))
    )
    (net (code "74") (name "unconnected-(U4-SENSOR_VN-Pad5)") (class "Default")
      (node (ref "U4") (pin "5") (pinfunction "SENSOR_VN_5") (pintype "input"))
    )
    (net (code "75") (name "unconnected-(U4-SENSOR_VP-Pad4)") (class "Default")
      (node (ref "U4") (pin "4") (pinfunction "SENSOR_VP_4") (pintype "input"))
    )
  )
)
